# SCH.net
KiCad netlist of a schematic drawn in EasyEDA Pro
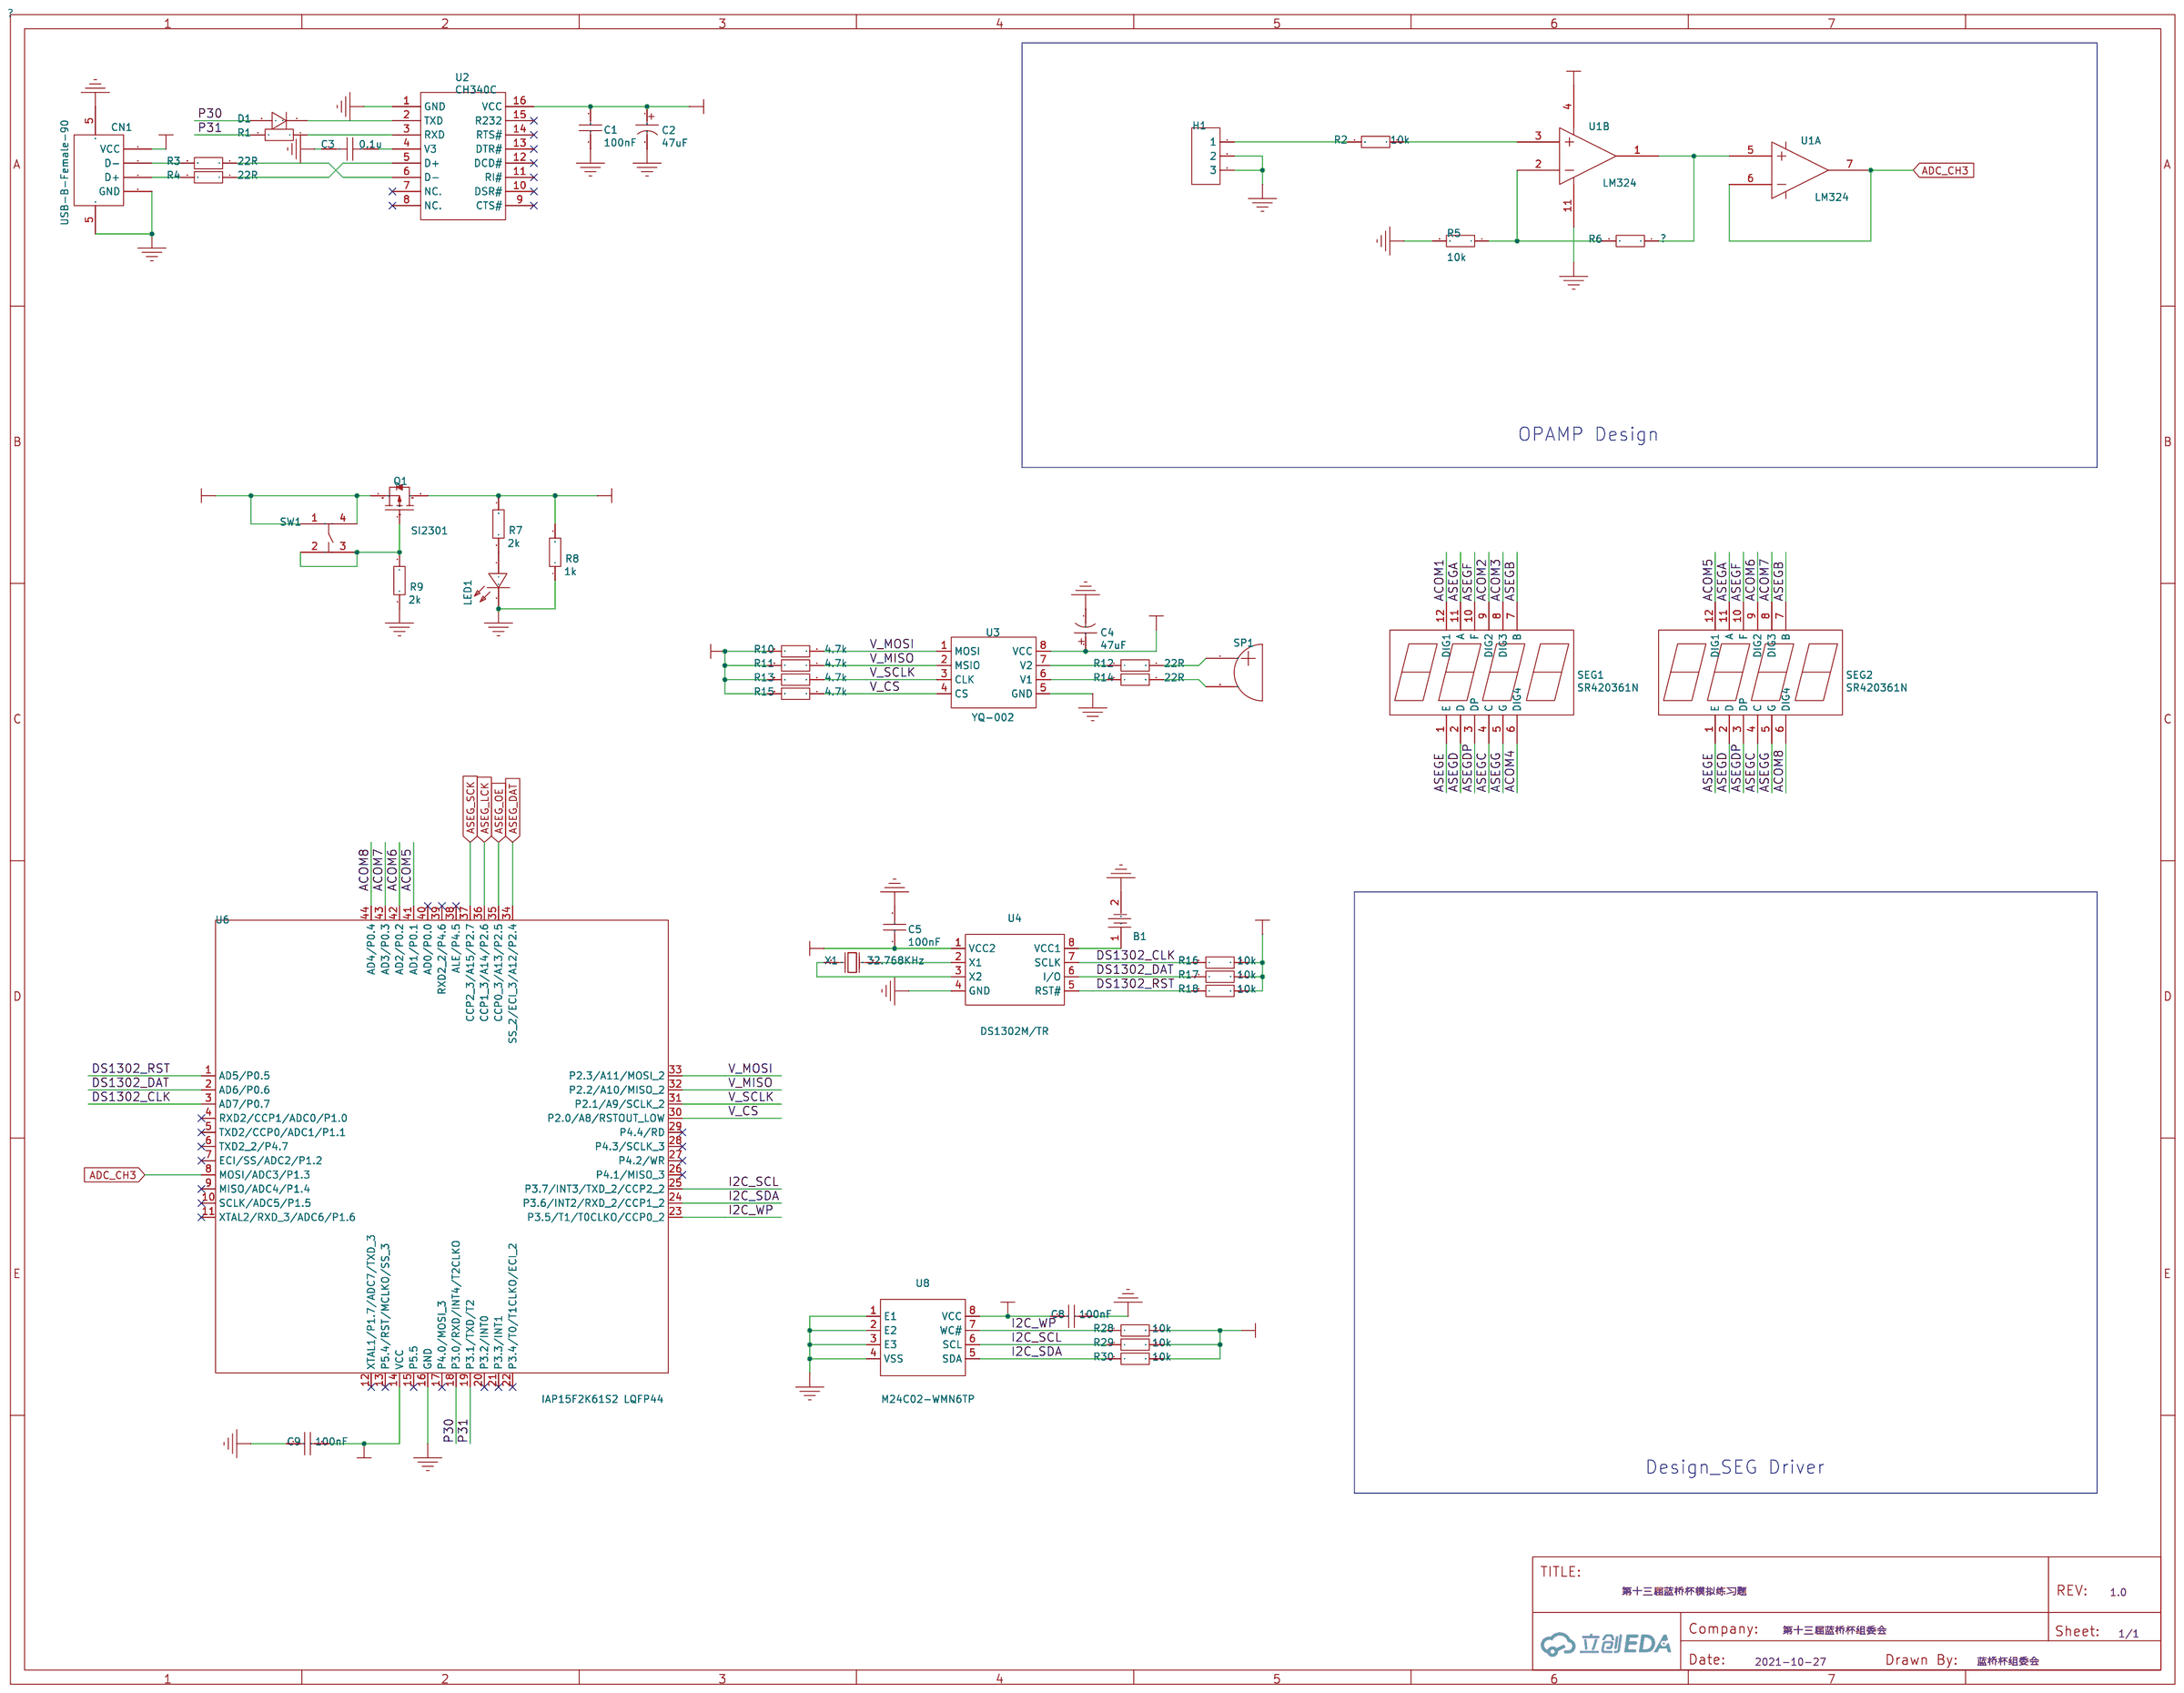
[diagram p0: schematic sheet]

(export (version "E")
  (design (tool "Eeschema 10.0.6"))
  (components
    (comp (ref "B1")
      (value "CR1220-2")
      (fields (field (name "Manufacturer") "Q&J"))
      (libsource (lib "easyedapro") (part "CR1220-2"))
    )
    (comp (ref "C1")
      (value "100nF")
      (fields (field (name "Manufacturer Part") "0805F104M500NT") (field (name "Manufacturer") "FH"))
      (libsource (lib "easyedapro") (part "100nF"))
    )
    (comp (ref "C2")
      (value "47uF")
      (fields (field (name "Manufacturer Part") "VES470M1HTR-0607") (field (name "Manufacturer") "LELON"))
      (libsource (lib "easyedapro") (part "47uF"))
    )
    (comp (ref "C3") (value "0.1u") (libsource (lib "easyedapro") (part "0.1u")))
    (comp (ref "C4")
      (value "47uF")
      (fields (field (name "Manufacturer Part") "VES470M1HTR-0607") (field (name "Manufacturer") "LELON"))
      (libsource (lib "easyedapro") (part "47uF"))
    )
    (comp (ref "C5")
      (value "100nF")
      (fields (field (name "Manufacturer Part") "0805F104M500NT") (field (name "Manufacturer") "FH"))
      (libsource (lib "easyedapro") (part "100nF"))
    )
    (comp (ref "C8")
      (value "100nF")
      (fields (field (name "Manufacturer Part") "0805F104M500NT") (field (name "Manufacturer") "FH"))
      (libsource (lib "easyedapro") (part "100nF"))
    )
    (comp (ref "C9")
      (value "100nF")
      (fields (field (name "Manufacturer Part") "0805F104M500NT") (field (name "Manufacturer") "FH"))
      (libsource (lib "easyedapro") (part "100nF"))
    )
    (comp (ref "CN1")
      (value "USB-B-Female-90")
      (fields (field (name "Manufacturer Part") "USB-BF90") (field (name "Manufacturer") "ValuePro"))
      (libsource (lib "easyedapro") (part "USB-B-Female-90"))
    )
    (comp (ref "D1")
      (value "KLL4148")
      (fields (field (name "Manufacturer") "KEXIN"))
      (libsource (lib "easyedapro") (part "KLL4148"))
    )
    (comp (ref "H1") (value "HDR-F-2.54_1x3") (libsource (lib "easyedapro") (part "HDR-F-2.54_1x3")))
    (comp (ref "LED1")
      (value "17-21URC/TR8")
      (fields (field (name "Manufacturer") "Everlight Elec"))
      (libsource (lib "easyedapro") (part "17-21URC/TR8"))
    )
    (comp (ref "Q1")
      (value "SI2301")
      (fields (field (name "Manufacturer") "Hottech"))
      (libsource (lib "easyedapro") (part "SI2301"))
    )
    (comp (ref "R1")
      (value "1k")
      (fields (field (name "Manufacturer Part") "080500J0104T5E") (field (name "Manufacturer") "UniOhm"))
      (libsource (lib "easyedapro") (part "22R"))
    )
    (comp (ref "R2")
      (value "10k")
      (fields (field (name "Manufacturer Part") "080500J0104T5E") (field (name "Manufacturer") "UniOhm"))
      (libsource (lib "easyedapro") (part "22R"))
    )
    (comp (ref "R3")
      (value "22R")
      (fields (field (name "Manufacturer Part") "080500J0104T5E") (field (name "Manufacturer") "UniOhm"))
      (libsource (lib "easyedapro") (part "22R"))
    )
    (comp (ref "R4")
      (value "22R")
      (fields (field (name "Manufacturer Part") "080500J0104T5E") (field (name "Manufacturer") "UniOhm"))
      (libsource (lib "easyedapro") (part "22R"))
    )
    (comp (ref "R5")
      (value "10k")
      (fields (field (name "Manufacturer Part") "080500J0104T5E") (field (name "Manufacturer") "UniOhm"))
      (libsource (lib "easyedapro") (part "22R"))
    )
    (comp (ref "R6")
      (value "？")
      (fields (field (name "Manufacturer Part") "080500J0104T5E") (field (name "Manufacturer") "UniOhm"))
      (libsource (lib "easyedapro") (part "22R"))
    )
    (comp (ref "R7")
      (value "2k")
      (fields (field (name "Manufacturer Part") "080500J0104T5E") (field (name "Manufacturer") "UniOhm"))
      (libsource (lib "easyedapro") (part "22R"))
    )
    (comp (ref "R8")
      (value "1k")
      (fields (field (name "Manufacturer Part") "080500J0104T5E") (field (name "Manufacturer") "UniOhm"))
      (libsource (lib "easyedapro") (part "22R"))
    )
    (comp (ref "R9")
      (value "2k")
      (fields (field (name "Manufacturer Part") "080500J0104T5E") (field (name "Manufacturer") "UniOhm"))
      (libsource (lib "easyedapro") (part "22R"))
    )
    (comp (ref "R10")
      (value "4.7k")
      (fields (field (name "Manufacturer Part") "080500J0104T5E") (field (name "Manufacturer") "UniOhm"))
      (libsource (lib "easyedapro") (part "22R"))
    )
    (comp (ref "R11")
      (value "4.7k")
      (fields (field (name "Manufacturer Part") "080500J0104T5E") (field (name "Manufacturer") "UniOhm"))
      (libsource (lib "easyedapro") (part "22R"))
    )
    (comp (ref "R12")
      (value "22R")
      (fields (field (name "Manufacturer Part") "080500J0104T5E") (field (name "Manufacturer") "UniOhm"))
      (libsource (lib "easyedapro") (part "22R"))
    )
    (comp (ref "R13")
      (value "4.7k")
      (fields (field (name "Manufacturer Part") "080500J0104T5E") (field (name "Manufacturer") "UniOhm"))
      (libsource (lib "easyedapro") (part "22R"))
    )
    (comp (ref "R14")
      (value "22R")
      (fields (field (name "Manufacturer Part") "080500J0104T5E") (field (name "Manufacturer") "UniOhm"))
      (libsource (lib "easyedapro") (part "22R"))
    )
    (comp (ref "R15")
      (value "4.7k")
      (fields (field (name "Manufacturer Part") "080500J0104T5E") (field (name "Manufacturer") "UniOhm"))
      (libsource (lib "easyedapro") (part "22R"))
    )
    (comp (ref "R16")
      (value "10k")
      (fields (field (name "Manufacturer Part") "080500J0104T5E") (field (name "Manufacturer") "UniOhm"))
      (libsource (lib "easyedapro") (part "22R"))
    )
    (comp (ref "R17")
      (value "10k")
      (fields (field (name "Manufacturer Part") "080500J0104T5E") (field (name "Manufacturer") "UniOhm"))
      (libsource (lib "easyedapro") (part "22R"))
    )
    (comp (ref "R18")
      (value "10k")
      (fields (field (name "Manufacturer Part") "080500J0104T5E") (field (name "Manufacturer") "UniOhm"))
      (libsource (lib "easyedapro") (part "22R"))
    )
    (comp (ref "R28")
      (value "10k")
      (fields (field (name "Manufacturer Part") "080500J0104T5E") (field (name "Manufacturer") "UniOhm"))
      (libsource (lib "easyedapro") (part "22R"))
    )
    (comp (ref "R29")
      (value "10k")
      (fields (field (name "Manufacturer Part") "080500J0104T5E") (field (name "Manufacturer") "UniOhm"))
      (libsource (lib "easyedapro") (part "22R"))
    )
    (comp (ref "R30")
      (value "10k")
      (fields (field (name "Manufacturer Part") "080500J0104T5E") (field (name "Manufacturer") "UniOhm"))
      (libsource (lib "easyedapro") (part "22R"))
    )
    (comp (ref "SEG1")
      (value "SR420361N")
      (fields (field (name "Manufacturer") "Wuxi ARK Tech Elec"))
      (libsource (lib "easyedapro") (part "SR420361N"))
    )
    (comp (ref "SEG2")
      (value "SR420361N")
      (fields (field (name "Manufacturer") "Wuxi ARK Tech Elec"))
      (libsource (lib "easyedapro") (part "SR420361N"))
    )
    (comp (ref "SP1") (value "BUZZER") (libsource (lib "easyedapro") (part "BUZZER")))
    (comp (ref "SW1")
      (value "TS-1159UB-B-D-BL")
      (fields (field (name "Manufacturer") "XKB Connectivity"))
      (libsource (lib "easyedapro") (part "TS-1159UB-B-D-BL"))
    )
    (comp (ref "U1") (value "LM324") (libsource (lib "easyedapro") (part "LM324")))
    (comp (ref "U2")
      (value "CH340C")
      (fields (field (name "Manufacturer") "WCH"))
      (libsource (lib "easyedapro") (part "CH340C"))
    )
    (comp (ref "U3") (value "YQ-002") (libsource (lib "easyedapro") (part "YQ-002")))
    (comp (ref "U4")
      (value "DS1302M/TR")
      (fields (field (name "Manufacturer") "HGSEMI"))
      (libsource (lib "easyedapro") (part "DS1302M/TR"))
    )
    (comp (ref "U6")
      (value "IAP15F2K61S2 LQFP44")
      (fields (field (name "Manufacturer") "STC"))
      (libsource (lib "easyedapro") (part "IAP15F2K61S2 LQFP44"))
    )
    (comp (ref "U8")
      (value "M24C02-WMN6TP")
      (fields (field (name "Manufacturer") "STMicroelectronics"))
      (libsource (lib "easyedapro") (part "M24C02-WMN6TP"))
    )
    (comp (ref "X1")
      (value "32.768KHz")
      (fields
        (field (name "Manufacturer Part") "6K832768F12UB")
        (field (name "Manufacturer") "SHENZHEN CRYSTAL TECH")
      )
      (libsource (lib "easyedapro") (part "32.768KHz"))
    )
  )
  (nets
    (net (code "1") (name "/ACOM1") (class "Default")
      (node (ref "SEG1") (pin "12") (pinfunction "DIG1_12") (pintype "unspecified"))
    )
    (net (code "2") (name "/ACOM2") (class "Default")
      (node (ref "SEG1") (pin "9") (pinfunction "DIG2_9") (pintype "unspecified"))
    )
    (net (code "3") (name "/ACOM3") (class "Default")
      (node (ref "SEG1") (pin "8") (pinfunction "DIG3_8") (pintype "unspecified"))
    )
    (net (code "4") (name "/ACOM4") (class "Default")
      (node (ref "SEG1") (pin "6") (pinfunction "DIG4_6") (pintype "unspecified"))
    )
    (net (code "5") (name "/ACOM5") (class "Default")
      (node (ref "SEG2") (pin "12") (pinfunction "DIG1_12") (pintype "unspecified"))
      (node (ref "U6") (pin "41") (pinfunction "AD1/P0.1_41") (pintype "unspecified"))
    )
    (net (code "6") (name "/ACOM6") (class "Default")
      (node (ref "SEG2") (pin "9") (pinfunction "DIG2_9") (pintype "unspecified"))
      (node (ref "U6") (pin "42") (pinfunction "AD2/P0.2_42") (pintype "unspecified"))
    )
    (net (code "7") (name "/ACOM7") (class "Default")
      (node (ref "SEG2") (pin "8") (pinfunction "DIG3_8") (pintype "unspecified"))
      (node (ref "U6") (pin "43") (pinfunction "AD3/P0.3_43") (pintype "unspecified"))
    )
    (net (code "8") (name "/ACOM8") (class "Default")
      (node (ref "SEG2") (pin "6") (pinfunction "DIG4_6") (pintype "unspecified"))
      (node (ref "U6") (pin "44") (pinfunction "AD4/P0.4_44") (pintype "unspecified"))
    )
    (net (code "9") (name "/ASEGA") (class "Default")
      (node (ref "SEG1") (pin "11") (pinfunction "A_11") (pintype "unspecified"))
      (node (ref "SEG2") (pin "11") (pinfunction "A_11") (pintype "unspecified"))
    )
    (net (code "10") (name "/ASEGB") (class "Default")
      (node (ref "SEG1") (pin "7") (pinfunction "B_7") (pintype "unspecified"))
      (node (ref "SEG2") (pin "7") (pinfunction "B_7") (pintype "unspecified"))
    )
    (net (code "11") (name "/ASEGC") (class "Default")
      (node (ref "SEG1") (pin "4") (pinfunction "C_4") (pintype "unspecified"))
      (node (ref "SEG2") (pin "4") (pinfunction "C_4") (pintype "unspecified"))
    )
    (net (code "12") (name "/ASEGD") (class "Default")
      (node (ref "SEG1") (pin "2") (pinfunction "D_2") (pintype "unspecified"))
      (node (ref "SEG2") (pin "2") (pinfunction "D_2") (pintype "unspecified"))
    )
    (net (code "13") (name "/ASEGDP") (class "Default")
      (node (ref "SEG1") (pin "3") (pinfunction "DP_3") (pintype "unspecified"))
      (node (ref "SEG2") (pin "3") (pinfunction "DP_3") (pintype "unspecified"))
    )
    (net (code "14") (name "/ASEGE") (class "Default")
      (node (ref "SEG1") (pin "1") (pinfunction "E_1") (pintype "unspecified"))
      (node (ref "SEG2") (pin "1") (pinfunction "E_1") (pintype "unspecified"))
    )
    (net (code "15") (name "/ASEGF") (class "Default")
      (node (ref "SEG1") (pin "10") (pinfunction "F_10") (pintype "unspecified"))
      (node (ref "SEG2") (pin "10") (pinfunction "F_10") (pintype "unspecified"))
    )
    (net (code "16") (name "/ASEGG") (class "Default")
      (node (ref "SEG1") (pin "5") (pinfunction "G_5") (pintype "unspecified"))
      (node (ref "SEG2") (pin "5") (pinfunction "G_5") (pintype "unspecified"))
    )
    (net (code "17") (name "/DS1302_CLK") (class "Default")
      (node (ref "R16") (pin "1") (pinfunction "1_1") (pintype "unspecified"))
      (node (ref "U4") (pin "7") (pinfunction "SCLK_7") (pintype "unspecified"))
      (node (ref "U6") (pin "3") (pinfunction "AD7/P0.7_3") (pintype "unspecified"))
    )
    (net (code "18") (name "/DS1302_DAT") (class "Default")
      (node (ref "R17") (pin "1") (pinfunction "1_1") (pintype "unspecified"))
      (node (ref "U4") (pin "6") (pinfunction "I/O_6") (pintype "unspecified"))
      (node (ref "U6") (pin "2") (pinfunction "AD6/P0.6_2") (pintype "unspecified"))
    )
    (net (code "19") (name "/DS1302_RST") (class "Default")
      (node (ref "R18") (pin "1") (pinfunction "1_1") (pintype "unspecified"))
      (node (ref "U4") (pin "5") (pinfunction "RST#_5") (pintype "unspecified"))
      (node (ref "U6") (pin "1") (pinfunction "AD5/P0.5_1") (pintype "unspecified"))
    )
    (net (code "20") (name "/I2C_SCL") (class "Default")
      (node (ref "R29") (pin "1") (pinfunction "1_1") (pintype "unspecified"))
      (node (ref "U6") (pin "25") (pinfunction "P3.7/INT3/TXD_2/CCP2_2_25") (pintype "unspecified"))
      (node (ref "U8") (pin "6") (pinfunction "SCL_6") (pintype "unspecified"))
    )
    (net (code "21") (name "/I2C_SDA") (class "Default")
      (node (ref "R30") (pin "1") (pinfunction "1_1") (pintype "unspecified"))
      (node (ref "U6") (pin "24") (pinfunction "P3.6/INT2/RXD_2/CCP1_2_24") (pintype "unspecified"))
      (node (ref "U8") (pin "5") (pinfunction "SDA_5") (pintype "unspecified"))
    )
    (net (code "22") (name "/I2C_WP") (class "Default")
      (node (ref "R28") (pin "1") (pinfunction "1_1") (pintype "unspecified"))
      (node (ref "U6") (pin "23") (pinfunction "P3.5/T1/T0CLKO/CCP0_2_23") (pintype "unspecified"))
      (node (ref "U8") (pin "7") (pinfunction "WC#_7") (pintype "unspecified"))
    )
    (net (code "23") (name "/P30") (class "Default")
      (node (ref "D1") (pin "2") (pinfunction "A_2") (pintype "unspecified"))
      (node (ref "U6") (pin "18") (pinfunction "P3.0/RXD/INT4/T2CLKO_18") (pintype "unspecified"))
    )
    (net (code "24") (name "/P31") (class "Default")
      (node (ref "R1") (pin "2") (pinfunction "2_2") (pintype "unspecified"))
      (node (ref "U6") (pin "19") (pinfunction "P3.1/TXD/T2_19") (pintype "unspecified"))
    )
    (net (code "25") (name "/V_CS") (class "Default")
      (node (ref "R15") (pin "1") (pinfunction "1_1") (pintype "unspecified"))
      (node (ref "U3") (pin "4") (pinfunction "CS_4") (pintype "unspecified"))
      (node (ref "U6") (pin "30") (pinfunction "P2.0/A8/RSTOUT_LOW_30") (pintype "unspecified"))
    )
    (net (code "26") (name "/V_MISO") (class "Default")
      (node (ref "R11") (pin "1") (pinfunction "1_1") (pintype "unspecified"))
      (node (ref "U3") (pin "2") (pinfunction "MSIO_2") (pintype "unspecified"))
      (node (ref "U6") (pin "32") (pinfunction "P2.2/A10/MISO_2_32") (pintype "unspecified"))
    )
    (net (code "27") (name "/V_MOSI") (class "Default")
      (node (ref "R10") (pin "1") (pinfunction "1_1") (pintype "unspecified"))
      (node (ref "U3") (pin "1") (pinfunction "MOSI_1") (pintype "unspecified"))
      (node (ref "U6") (pin "33") (pinfunction "P2.3/A11/MOSI_2_33") (pintype "unspecified"))
    )
    (net (code "28") (name "/V_SCLK") (class "Default")
      (node (ref "R13") (pin "1") (pinfunction "1_1") (pintype "unspecified"))
      (node (ref "U3") (pin "3") (pinfunction "CLK_3") (pintype "unspecified"))
      (node (ref "U6") (pin "31") (pinfunction "P2.1/A9/SCLK_2_31") (pintype "unspecified"))
    )
    (net (code "29") (name "ADC_CH3") (class "Default")
      (node (ref "U1") (pin "6") (pintype "unspecified"))
      (node (ref "U1") (pin "7") (pintype "unspecified"))
      (node (ref "U6") (pin "8") (pinfunction "MOSI/ADC3/P1.3_8") (pintype "unspecified"))
    )
    (net (code "30") (name "ASEG_DAT") (class "Default")
      (node (ref "U6") (pin "34") (pinfunction "SS_2/ECI_3/A12/P2.4_34") (pintype "unspecified"))
    )
    (net (code "31") (name "ASEG_LCK") (class "Default")
      (node (ref "U6") (pin "36") (pinfunction "CCP1_3/A14/P2.6_36") (pintype "unspecified"))
    )
    (net (code "32") (name "ASEG_OE") (class "Default")
      (node (ref "U6") (pin "35") (pinfunction "CCP0_3/A13/P2.5_35") (pintype "unspecified"))
    )
    (net (code "33") (name "ASEG_SCK") (class "Default")
      (node (ref "U6") (pin "37") (pinfunction "CCP2_3/A15/P2.7_37") (pintype "unspecified"))
    )
    (net (code "34") (name "GND") (class "Default")
      (node (ref "B1") (pin "2") (pinfunction "2_2") (pintype "unspecified"))
      (node (ref "C1") (pin "1") (pinfunction "1_1") (pintype "unspecified"))
      (node (ref "C2") (pin "2") (pinfunction "2_2") (pintype "input"))
      (node (ref "C3") (pin "1") (pinfunction "1_1") (pintype "unspecified"))
      (node (ref "C4") (pin "2") (pinfunction "2_2") (pintype "input"))
      (node (ref "C5") (pin "2") (pinfunction "2_2") (pintype "unspecified"))
      (node (ref "C8") (pin "2") (pinfunction "2_2") (pintype "unspecified"))
      (node (ref "C9") (pin "1") (pinfunction "1_1") (pintype "unspecified"))
      (node (ref "CN1") (pin "4") (pinfunction "GND_4") (pintype "unspecified"))
      (node (ref "CN1") (pin "5") (pinfunction "SH2_5") (pintype "unspecified"))
      (node (ref "H1") (pin "2") (pinfunction "2_2") (pintype "unspecified"))
      (node (ref "H1") (pin "3") (pinfunction "3_3") (pintype "unspecified"))
      (node (ref "LED1") (pin "2") (pinfunction "K_2") (pintype "unspecified"))
      (node (ref "R5") (pin "2") (pinfunction "2_2") (pintype "unspecified"))
      (node (ref "R8") (pin "1") (pinfunction "1_1") (pintype "unspecified"))
      (node (ref "R9") (pin "1") (pinfunction "1_1") (pintype "unspecified"))
      (node (ref "U1") (pin "11") (pintype "unspecified"))
      (node (ref "U2") (pin "1") (pinfunction "GND_1") (pintype "unspecified"))
      (node (ref "U3") (pin "5") (pinfunction "GND_5") (pintype "unspecified"))
      (node (ref "U4") (pin "4") (pinfunction "GND_4") (pintype "unspecified"))
      (node (ref "U6") (pin "16") (pinfunction "GND_16") (pintype "unspecified"))
      (node (ref "U8") (pin "1") (pinfunction "E1_1") (pintype "unspecified"))
      (node (ref "U8") (pin "2") (pinfunction "E2_2") (pintype "unspecified"))
      (node (ref "U8") (pin "3") (pinfunction "E3_3") (pintype "unspecified"))
      (node (ref "U8") (pin "4") (pinfunction "VSS_4") (pintype "unspecified"))
    )
    (net (code "35") (name "Net-(CN1-D+)") (class "Default")
      (node (ref "CN1") (pin "3") (pinfunction "D+_3") (pintype "unspecified"))
      (node (ref "R4") (pin "2") (pinfunction "2_2") (pintype "unspecified"))
    )
    (net (code "36") (name "Net-(CN1-D-)") (class "Default")
      (node (ref "CN1") (pin "2") (pinfunction "D-_2") (pintype "unspecified"))
      (node (ref "R3") (pin "2") (pinfunction "2_2") (pintype "unspecified"))
    )
    (net (code "37") (name "Net-(D1-C)") (class "Default")
      (node (ref "D1") (pin "1") (pinfunction "C_1") (pintype "unspecified"))
      (node (ref "U2") (pin "2") (pinfunction "TXD_2") (pintype "unspecified"))
    )
    (net (code "38") (name "Net-(H1-Pad1)") (class "Default")
      (node (ref "H1") (pin "1") (pinfunction "1_1") (pintype "unspecified"))
      (node (ref "R2") (pin "2") (pinfunction "2_2") (pintype "unspecified"))
    )
    (net (code "39") (name "Net-(LED1-A)") (class "Default")
      (node (ref "LED1") (pin "1") (pinfunction "A_1") (pintype "unspecified"))
      (node (ref "R7") (pin "1") (pinfunction "1_1") (pintype "unspecified"))
    )
    (net (code "40") (name "Net-(Q1-G)") (class "Default")
      (node (ref "Q1") (pin "1") (pinfunction "G_1") (pintype "unspecified"))
      (node (ref "R9") (pin "2") (pinfunction "2_2") (pintype "unspecified"))
      (node (ref "SW1") (pin "2") (pinfunction "4_2") (pintype "unspecified"))
      (node (ref "SW1") (pin "3") (pinfunction "3_3") (pintype "unspecified"))
    )
    (net (code "41") (name "Net-(R2-Pad1)") (class "Default")
      (node (ref "R2") (pin "1") (pinfunction "1_1") (pintype "unspecified"))
      (node (ref "U1") (pin "3") (pintype "unspecified"))
    )
    (net (code "42") (name "Net-(R5-Pad1)") (class "Default")
      (node (ref "R5") (pin "1") (pinfunction "1_1") (pintype "unspecified"))
      (node (ref "R6") (pin "2") (pinfunction "2_2") (pintype "unspecified"))
      (node (ref "U1") (pin "2") (pintype "unspecified"))
    )
    (net (code "43") (name "Net-(R6-Pad1)") (class "Default")
      (node (ref "R6") (pin "1") (pinfunction "1_1") (pintype "unspecified"))
      (node (ref "U1") (pin "1") (pintype "unspecified"))
      (node (ref "U1") (pin "5") (pintype "unspecified"))
    )
    (net (code "44") (name "Net-(R12-Pad2)") (class "Default")
      (node (ref "R12") (pin "2") (pinfunction "2_2") (pintype "unspecified"))
      (node (ref "SP1") (pin "1") (pinfunction "1_1") (pintype "unspecified"))
    )
    (net (code "45") (name "Net-(R14-Pad2)") (class "Default")
      (node (ref "R14") (pin "2") (pinfunction "2_2") (pintype "unspecified"))
      (node (ref "SP1") (pin "2") (pinfunction "2_2") (pintype "unspecified"))
    )
    (net (code "46") (name "Net-(U2-D+)") (class "Default")
      (node (ref "R4") (pin "1") (pinfunction "1_1") (pintype "unspecified"))
      (node (ref "U2") (pin "5") (pinfunction "D+_5") (pintype "unspecified"))
    )
    (net (code "47") (name "Net-(U2-D-)") (class "Default")
      (node (ref "R3") (pin "1") (pinfunction "1_1") (pintype "unspecified"))
      (node (ref "U2") (pin "6") (pinfunction "D-_6") (pintype "unspecified"))
    )
    (net (code "48") (name "Net-(U2-RXD)") (class "Default")
      (node (ref "R1") (pin "1") (pinfunction "1_1") (pintype "unspecified"))
      (node (ref "U2") (pin "3") (pinfunction "RXD_3") (pintype "unspecified"))
    )
    (net (code "49") (name "Net-(U2-V3)") (class "Default")
      (node (ref "C3") (pin "2") (pinfunction "2_2") (pintype "unspecified"))
      (node (ref "U2") (pin "4") (pinfunction "V3_4") (pintype "unspecified"))
    )
    (net (code "50") (name "Net-(U3-V1)") (class "Default")
      (node (ref "R14") (pin "1") (pinfunction "1_1") (pintype "unspecified"))
      (node (ref "U3") (pin "6") (pinfunction "V1_6") (pintype "unspecified"))
    )
    (net (code "51") (name "Net-(U3-V2)") (class "Default")
      (node (ref "R12") (pin "1") (pinfunction "1_1") (pintype "unspecified"))
      (node (ref "U3") (pin "7") (pinfunction "V2_7") (pintype "unspecified"))
    )
    (net (code "52") (name "Net-(U4-VCC1)") (class "Default")
      (node (ref "B1") (pin "1") (pinfunction "1_1") (pintype "unspecified"))
      (node (ref "U4") (pin "8") (pinfunction "VCC1_8") (pintype "unspecified"))
    )
    (net (code "53") (name "Net-(U4-X1)") (class "Default")
      (node (ref "U4") (pin "2") (pinfunction "X1_2") (pintype "unspecified"))
      (node (ref "X1") (pin "2") (pinfunction "OSC2_2") (pintype "unspecified"))
    )
    (net (code "54") (name "Net-(U4-X2)") (class "Default")
      (node (ref "U4") (pin "3") (pinfunction "X2_3") (pintype "unspecified"))
      (node (ref "X1") (pin "1") (pinfunction "OSC1_1") (pintype "unspecified"))
    )
    (net (code "55") (name "VDD_NODE_A") (class "Default")
      (node (ref "C4") (pin "1") (pinfunction "1_1") (pintype "input"))
      (node (ref "C5") (pin "1") (pinfunction "1_1") (pintype "unspecified"))
      (node (ref "C8") (pin "1") (pinfunction "1_1") (pintype "unspecified"))
      (node (ref "C9") (pin "2") (pinfunction "2_2") (pintype "unspecified"))
      (node (ref "Q1") (pin "3") (pinfunction "D_3") (pintype "unspecified"))
      (node (ref "R10") (pin "2") (pinfunction "2_2") (pintype "unspecified"))
      (node (ref "R11") (pin "2") (pinfunction "2_2") (pintype "unspecified"))
      (node (ref "R13") (pin "2") (pinfunction "2_2") (pintype "unspecified"))
      (node (ref "R15") (pin "2") (pinfunction "2_2") (pintype "unspecified"))
      (node (ref "R16") (pin "2") (pinfunction "2_2") (pintype "unspecified"))
      (node (ref "R17") (pin "2") (pinfunction "2_2") (pintype "unspecified"))
      (node (ref "R18") (pin "2") (pinfunction "2_2") (pintype "unspecified"))
      (node (ref "R28") (pin "2") (pinfunction "2_2") (pintype "unspecified"))
      (node (ref "R29") (pin "2") (pinfunction "2_2") (pintype "unspecified"))
      (node (ref "R30") (pin "2") (pinfunction "2_2") (pintype "unspecified"))
      (node (ref "R7") (pin "2") (pinfunction "2_2") (pintype "unspecified"))
      (node (ref "R8") (pin "2") (pinfunction "2_2") (pintype "unspecified"))
      (node (ref "U1") (pin "4") (pintype "unspecified"))
      (node (ref "U3") (pin "8") (pinfunction "VCC_8") (pintype "unspecified"))
      (node (ref "U4") (pin "1") (pinfunction "VCC2_1") (pintype "unspecified"))
      (node (ref "U6") (pin "14") (pinfunction "VCC_14") (pintype "unspecified"))
      (node (ref "U8") (pin "8") (pinfunction "VCC_8") (pintype "unspecified"))
    )
    (net (code "56") (name "VUSB") (class "Default")
      (node (ref "C1") (pin "2") (pinfunction "2_2") (pintype "unspecified"))
      (node (ref "C2") (pin "1") (pinfunction "1_1") (pintype "input"))
      (node (ref "CN1") (pin "1") (pinfunction "VCC_1") (pintype "unspecified"))
      (node (ref "Q1") (pin "2") (pinfunction "S_2") (pintype "unspecified"))
      (node (ref "SW1") (pin "1") (pinfunction "1_1") (pintype "unspecified"))
      (node (ref "SW1") (pin "4") (pinfunction "2_4") (pintype "unspecified"))
      (node (ref "U2") (pin "16") (pinfunction "VCC_16") (pintype "unspecified"))
    )
    (net (code "57") (name "unconnected-(U2-CTS#-Pad9)") (class "Default")
      (node (ref "U2") (pin "9") (pinfunction "CTS#_9") (pintype "unspecified+no_connect"))
    )
    (net (code "58") (name "unconnected-(U2-DCD#-Pad12)") (class "Default")
      (node (ref "U2") (pin "12") (pinfunction "DCD#_12") (pintype "unspecified+no_connect"))
    )
    (net (code "59") (name "unconnected-(U2-DSR#-Pad10)") (class "Default")
      (node (ref "U2") (pin "10") (pinfunction "DSR#_10") (pintype "unspecified+no_connect"))
    )
    (net (code "60") (name "unconnected-(U2-DTR#-Pad13)") (class "Default")
      (node (ref "U2") (pin "13") (pinfunction "DTR#_13") (pintype "unspecified+no_connect"))
    )
    (net (code "61") (name "unconnected-(U2-NC.-Pad7)") (class "Default")
      (node (ref "U2") (pin "7") (pinfunction "NC._7") (pintype "unspecified+no_connect"))
    )
    (net (code "62") (name "unconnected-(U2-NC.-Pad8)") (class "Default")
      (node (ref "U2") (pin "8") (pinfunction "NC._8") (pintype "unspecified+no_connect"))
    )
    (net (code "63") (name "unconnected-(U2-R232-Pad15)") (class "Default")
      (node (ref "U2") (pin "15") (pinfunction "R232_15") (pintype "unspecified+no_connect"))
    )
    (net (code "64") (name "unconnected-(U2-RI#-Pad11)") (class "Default")
      (node (ref "U2") (pin "11") (pinfunction "RI#_11") (pintype "unspecified+no_connect"))
    )
    (net (code "65") (name "unconnected-(U2-RTS#-Pad14)") (class "Default")
      (node (ref "U2") (pin "14") (pinfunction "RTS#_14") (pintype "unspecified+no_connect"))
    )
    (net (code "66") (name "unconnected-(U6-AD0{slash}P0.0-Pad40)") (class "Default")
      (node (ref "U6") (pin "40") (pinfunction "AD0/P0.0_40") (pintype "unspecified+no_connect"))
    )
    (net (code "67") (name "unconnected-(U6-ALE{slash}P4.5-Pad38)") (class "Default")
      (node (ref "U6") (pin "38") (pinfunction "ALE/P4.5_38") (pintype "unspecified+no_connect"))
    )
    (net (code "68") (name "unconnected-(U6-ECI{slash}SS{slash}ADC2{slash}P1.2-Pad7)") (class "Default")
      (node (ref "U6") (pin "7") (pinfunction "ECI/SS/ADC2/P1.2_7") (pintype "unspecified+no_connect"))
    )
    (net (code "69") (name "unconnected-(U6-MISO{slash}ADC4{slash}P1.4-Pad9)") (class "Default")
      (node (ref "U6") (pin "9") (pinfunction "MISO/ADC4/P1.4_9") (pintype "unspecified+no_connect"))
    )
    (net (code "70") (name "unconnected-(U6-P3.2{slash}INT0-Pad20)") (class "Default")
      (node (ref "U6") (pin "20") (pinfunction "P3.2/INT0_20") (pintype "unspecified+no_connect"))
    )
    (net (code "71") (name "unconnected-(U6-P3.3{slash}INT1-Pad21)") (class "Default")
      (node (ref "U6") (pin "21") (pinfunction "P3.3/INT1_21") (pintype "unspecified+no_connect"))
    )
    (net (code "72") (name "unconnected-(U6-P3.4{slash}T0{slash}T1CLKO{slash}ECI_2-Pad22)") (class "Default")
      (node (ref "U6") (pin "22") (pinfunction "P3.4/T0/T1CLKO/ECI_2_22") (pintype "unspecified+no_connect"))
    )
    (net (code "73") (name "unconnected-(U6-P4.0{slash}MOSI_3-Pad17)") (class "Default")
      (node (ref "U6") (pin "17") (pinfunction "P4.0/MOSI_3_17") (pintype "unspecified+no_connect"))
    )
    (net (code "74") (name "unconnected-(U6-P4.1{slash}MISO_3-Pad26)") (class "Default")
      (node (ref "U6") (pin "26") (pinfunction "P4.1/MISO_3_26") (pintype "unspecified+no_connect"))
    )
    (net (code "75") (name "unconnected-(U6-P4.2{slash}WR-Pad27)") (class "Default")
      (node (ref "U6") (pin "27") (pinfunction "P4.2/WR_27") (pintype "unspecified+no_connect"))
    )
    (net (code "76") (name "unconnected-(U6-P4.3{slash}SCLK_3-Pad28)") (class "Default")
      (node (ref "U6") (pin "28") (pinfunction "P4.3/SCLK_3_28") (pintype "unspecified+no_connect"))
    )
    (net (code "77") (name "unconnected-(U6-P4.4{slash}RD-Pad29)") (class "Default")
      (node (ref "U6") (pin "29") (pinfunction "P4.4/RD_29") (pintype "unspecified+no_connect"))
    )
    (net (code "78") (name "unconnected-(U6-P5.4{slash}RST{slash}MCLKO{slash}SS_3-Pad13)") (class "Default")
      (node (ref "U6") (pin "13") (pinfunction "P5.4/RST/MCLKO/SS_3_13") (pintype "unspecified+no_connect"))
    )
    (net (code "79") (name "unconnected-(U6-P5.5-Pad15)") (class "Default")
      (node (ref "U6") (pin "15") (pinfunction "P5.5_15") (pintype "unspecified+no_connect"))
    )
    (net (code "80") (name "unconnected-(U6-RXD2_2{slash}P4.6-Pad39)") (class "Default")
      (node (ref "U6") (pin "39") (pinfunction "RXD2_2/P4.6_39") (pintype "unspecified+no_connect"))
    )
    (net (code "81") (name "unconnected-(U6-RXD2{slash}CCP1{slash}ADC0{slash}P1.0-Pad4)") (class "Default")
      (node (ref "U6") (pin "4") (pinfunction "RXD2/CCP1/ADC0/P1.0_4") (pintype "unspecified+no_connect"))
    )
    (net (code "82") (name "unconnected-(U6-SCLK{slash}ADC5{slash}P1.5-Pad10)") (class "Default")
      (node (ref "U6") (pin "10") (pinfunction "SCLK/ADC5/P1.5_10") (pintype "unspecified+no_connect"))
    )
    (net (code "83") (name "unconnected-(U6-TXD2_2{slash}P4.7-Pad6)") (class "Default")
      (node (ref "U6") (pin "6") (pinfunction "TXD2_2/P4.7_6") (pintype "unspecified+no_connect"))
    )
    (net (code "84") (name "unconnected-(U6-TXD2{slash}CCP0{slash}ADC1{slash}P1.1-Pad5)") (class "Default")
      (node (ref "U6") (pin "5") (pinfunction "TXD2/CCP0/ADC1/P1.1_5") (pintype "unspecified+no_connect"))
    )
    (net (code "85") (name "unconnected-(U6-XTAL1{slash}P1.7{slash}ADC7{slash}TXD_3-Pad12)") (class "Default")
      (node (ref "U6") (pin "12") (pinfunction "XTAL1/P1.7/ADC7/TXD_3_12") (pintype "unspecified+no_connect"))
    )
    (net (code "86") (name "unconnected-(U6-XTAL2{slash}RXD_3{slash}ADC6{slash}P1.6-Pad11)") (class "Default")
      (node (ref "U6") (pin "11") (pinfunction "XTAL2/RXD_3/ADC6/P1.6_11") (pintype "unspecified+no_connect"))
    )
  )
)
